# LM2596-12V.net
KiCad netlist of a schematic drawn in Altium Designer
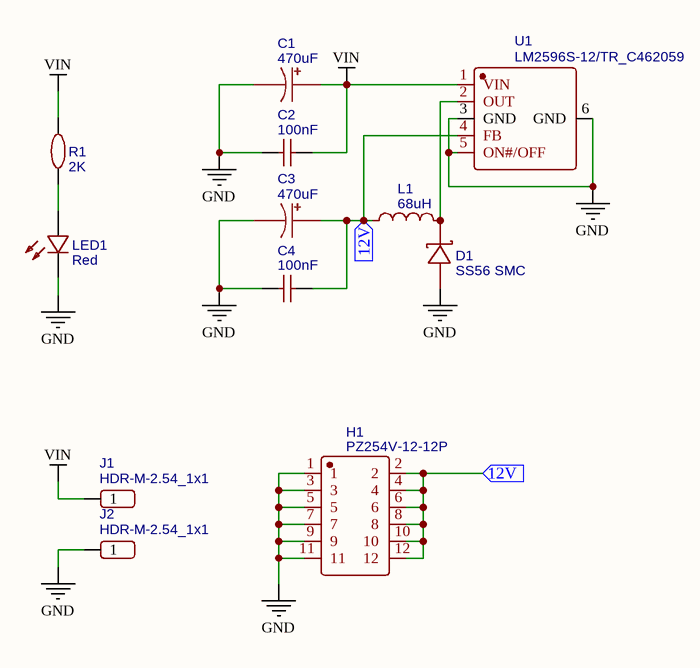
[diagram p0: LM2596-12V.SchDoc]

(export (version "E")
  (design (tool "Eeschema 10.0.6"))
  (components
    (comp (ref "C1")
      (value "470uF")
      (footprint "CM G(12.5*13.5)")
      (fields
        (field (name "BOM_MANUFACTURER PART") "VEJ471M1HTR-1316")
        (field (name "BOM_SUPPLIER PART") "C108926")
        (field (name "CONTRIBUTOR") "LCSC")
      )
      (libsource (lib "altium-import") (part "root_3_470uF_"))
    )
    (comp (ref "C2")
      (value "100nF")
      (footprint "C 1210_L")
      (fields
        (field (name "BOM_MANUFACTURER PART") "C1210X104K251T")
        (field (name "BOM_SUPPLIER PART") "C106103")
      )
      (libsource (lib "altium-import") (part "root_0_100nF_"))
    )
    (comp (ref "C3")
      (value "470uF")
      (footprint "CM G(12.5*13.5)")
      (fields
        (field (name "BOM_MANUFACTURER PART") "VEJ471M1HTR-1316")
        (field (name "BOM_SUPPLIER PART") "C108926")
        (field (name "CONTRIBUTOR") "LCSC")
      )
      (libsource (lib "altium-import") (part "root_3_470uF_"))
    )
    (comp (ref "C4")
      (value "100nF")
      (footprint "C 1210_L")
      (fields
        (field (name "BOM_MANUFACTURER PART") "C1210X104K251T")
        (field (name "BOM_SUPPLIER PART") "C106103")
      )
      (libsource (lib "altium-import") (part "root_0_100nF_"))
    )
    (comp (ref "D1")
      (value "SS56 SMC")
      (footprint "SMC")
      (fields (field (name "BOM_SUPPLIER PART") "C24138"))
      (libsource (lib "altium-import") (part "root_1_SS56 SMC_"))
    )
    (comp (ref "H1")
      (value "PZ254V-12-12P")
      (footprint "其他各种PCB封装:HDR2X6")
      (fields (field (name "BOM_SUPPLIER PART") "C492423") (field (name "CONTRIBUTOR") "LCSC"))
      (libsource (lib "altium-import") (part "root_0_PZ254V-12-12P_"))
    )
    (comp (ref "J1")
      (value "HDR-M-2.54_1x1")
      (footprint "Miscellaneous Connectors:PIN1")
      (fields (field (name "BOM_SUPPLIER PART") "C81276") (field (name "CONTRIBUTOR") "LCEDA_Lib"))
      (libsource (lib "altium-import") (part "root_0_HDR-M-2.54_1x1_"))
    )
    (comp (ref "J2")
      (value "HDR-M-2.54_1x1")
      (footprint "Miscellaneous Connectors:PIN1")
      (fields (field (name "BOM_SUPPLIER PART") "C81276") (field (name "CONTRIBUTOR") "LCEDA_Lib"))
      (libsource (lib "altium-import") (part "root_0_HDR-M-2.54_1x1_"))
    )
    (comp (ref "L1")
      (value "68uH")
      (footprint "CDRH127")
      (fields (field (name "BOM_SUPPLIER PART") "C497902") (field (name "CONTRIBUTOR") "LCSC"))
      (libsource (lib "altium-import") (part "root_0_68uH_"))
    )
    (comp (ref "LED1")
      (value "Red")
      (footprint "LED,数码管,显示屏,点阵,蜂鸣器:LED 0805R")
      (fields
        (field (name "BOM_MANUFACTURER PART") "17-21SURC/S530-A3/TR8")
        (field (name "BOM_SUPPLIER PART") "C72037")
      )
      (libsource (lib "altium-import") (part "root_1_17-21SURC/S530-A3/TR8_"))
    )
    (comp (ref "R1")
      (value "2K")
      (footprint "R0805")
      (fields
        (field (name "BOM_MANUFACTURER PART") "0805W8J0202T5E")
        (field (name "BOM_SUPPLIER PART") "C1359")
      )
      (libsource (lib "altium-import") (part "root_1_2K_"))
    )
    (comp (ref "U1")
      (value "LM2596S-12/TR_C462059")
      (footprint "三极管SOT,TO直插元件封装:TO263-5")
      (fields
        (field (name "BOM_SUPPLIER PART") "C462059")
        (field (name "BOM_MANUFACTURER PART") "LM2596S-12/TR")
        (field (name "CONTRIBUTOR") "LCSC")
      )
      (libsource (lib "altium-import") (part "root_0_LM2596S-12/TR_C462059_"))
    )
  )
  (nets
    (net (code "1") (name "/12V") (class "Default")
      (node (ref "C3") (pin "1") (pinfunction "1_1") (pintype "passive"))
      (node (ref "C4") (pin "2") (pinfunction "2_2") (pintype "passive"))
      (node (ref "H1") (pin "10") (pinfunction "10_10") (pintype "passive"))
      (node (ref "H1") (pin "12") (pinfunction "12_12") (pintype "passive"))
      (node (ref "H1") (pin "2") (pinfunction "2_2") (pintype "passive"))
      (node (ref "H1") (pin "4") (pinfunction "4_4") (pintype "passive"))
      (node (ref "H1") (pin "6") (pinfunction "6_6") (pintype "passive"))
      (node (ref "H1") (pin "8") (pinfunction "8_8") (pintype "passive"))
      (node (ref "L1") (pin "1") (pinfunction "1_1") (pintype "passive"))
      (node (ref "U1") (pin "4") (pinfunction "FB_4") (pintype "passive"))
    )
    (net (code "2") (name "GND") (class "Default")
      (node (ref "C1") (pin "2") (pinfunction "2_2") (pintype "passive"))
      (node (ref "C2") (pin "1") (pinfunction "1_1") (pintype "passive"))
      (node (ref "C3") (pin "2") (pinfunction "2_2") (pintype "passive"))
      (node (ref "C4") (pin "1") (pinfunction "1_1") (pintype "passive"))
      (node (ref "D1") (pin "1") (pinfunction "A_1") (pintype "passive"))
      (node (ref "H1") (pin "1") (pinfunction "1_1") (pintype "passive"))
      (node (ref "H1") (pin "11") (pinfunction "11_11") (pintype "passive"))
      (node (ref "H1") (pin "3") (pinfunction "3_3") (pintype "passive"))
      (node (ref "H1") (pin "5") (pinfunction "5_5") (pintype "passive"))
      (node (ref "H1") (pin "7") (pinfunction "7_7") (pintype "passive"))
      (node (ref "H1") (pin "9") (pinfunction "9_9") (pintype "passive"))
      (node (ref "J2") (pin "1") (pinfunction "1_1") (pintype "passive"))
      (node (ref "LED1") (pin "2") (pinfunction "C_2") (pintype "passive"))
      (node (ref "U1") (pin "3") (pinfunction "GND_3") (pintype "passive"))
      (node (ref "U1") (pin "5") (pinfunction "ON#/OFF_5") (pintype "passive"))
      (node (ref "U1") (pin "6") (pinfunction "GND_6") (pintype "passive"))
    )
    (net (code "3") (name "Net-(D1-K)") (class "Default")
      (node (ref "D1") (pin "2") (pinfunction "K_2") (pintype "passive"))
      (node (ref "L1") (pin "2") (pinfunction "2_2") (pintype "passive"))
      (node (ref "U1") (pin "2") (pinfunction "OUT_2") (pintype "passive"))
    )
    (net (code "4") (name "Net-(LED1-A)") (class "Default")
      (node (ref "LED1") (pin "1") (pinfunction "A_1") (pintype "passive"))
      (node (ref "R1") (pin "1") (pinfunction "1_1") (pintype "passive"))
    )
    (net (code "5") (name "VIN") (class "Default")
      (node (ref "C1") (pin "1") (pinfunction "1_1") (pintype "passive"))
      (node (ref "C2") (pin "2") (pinfunction "2_2") (pintype "passive"))
      (node (ref "J1") (pin "1") (pinfunction "1_1") (pintype "passive"))
      (node (ref "R1") (pin "2") (pinfunction "2_2") (pintype "passive"))
      (node (ref "U1") (pin "1") (pinfunction "VIN_1") (pintype "passive"))
    )
  )
)
